# Source_Files.net
KiCad netlist of a schematic drawn in EasyEDA
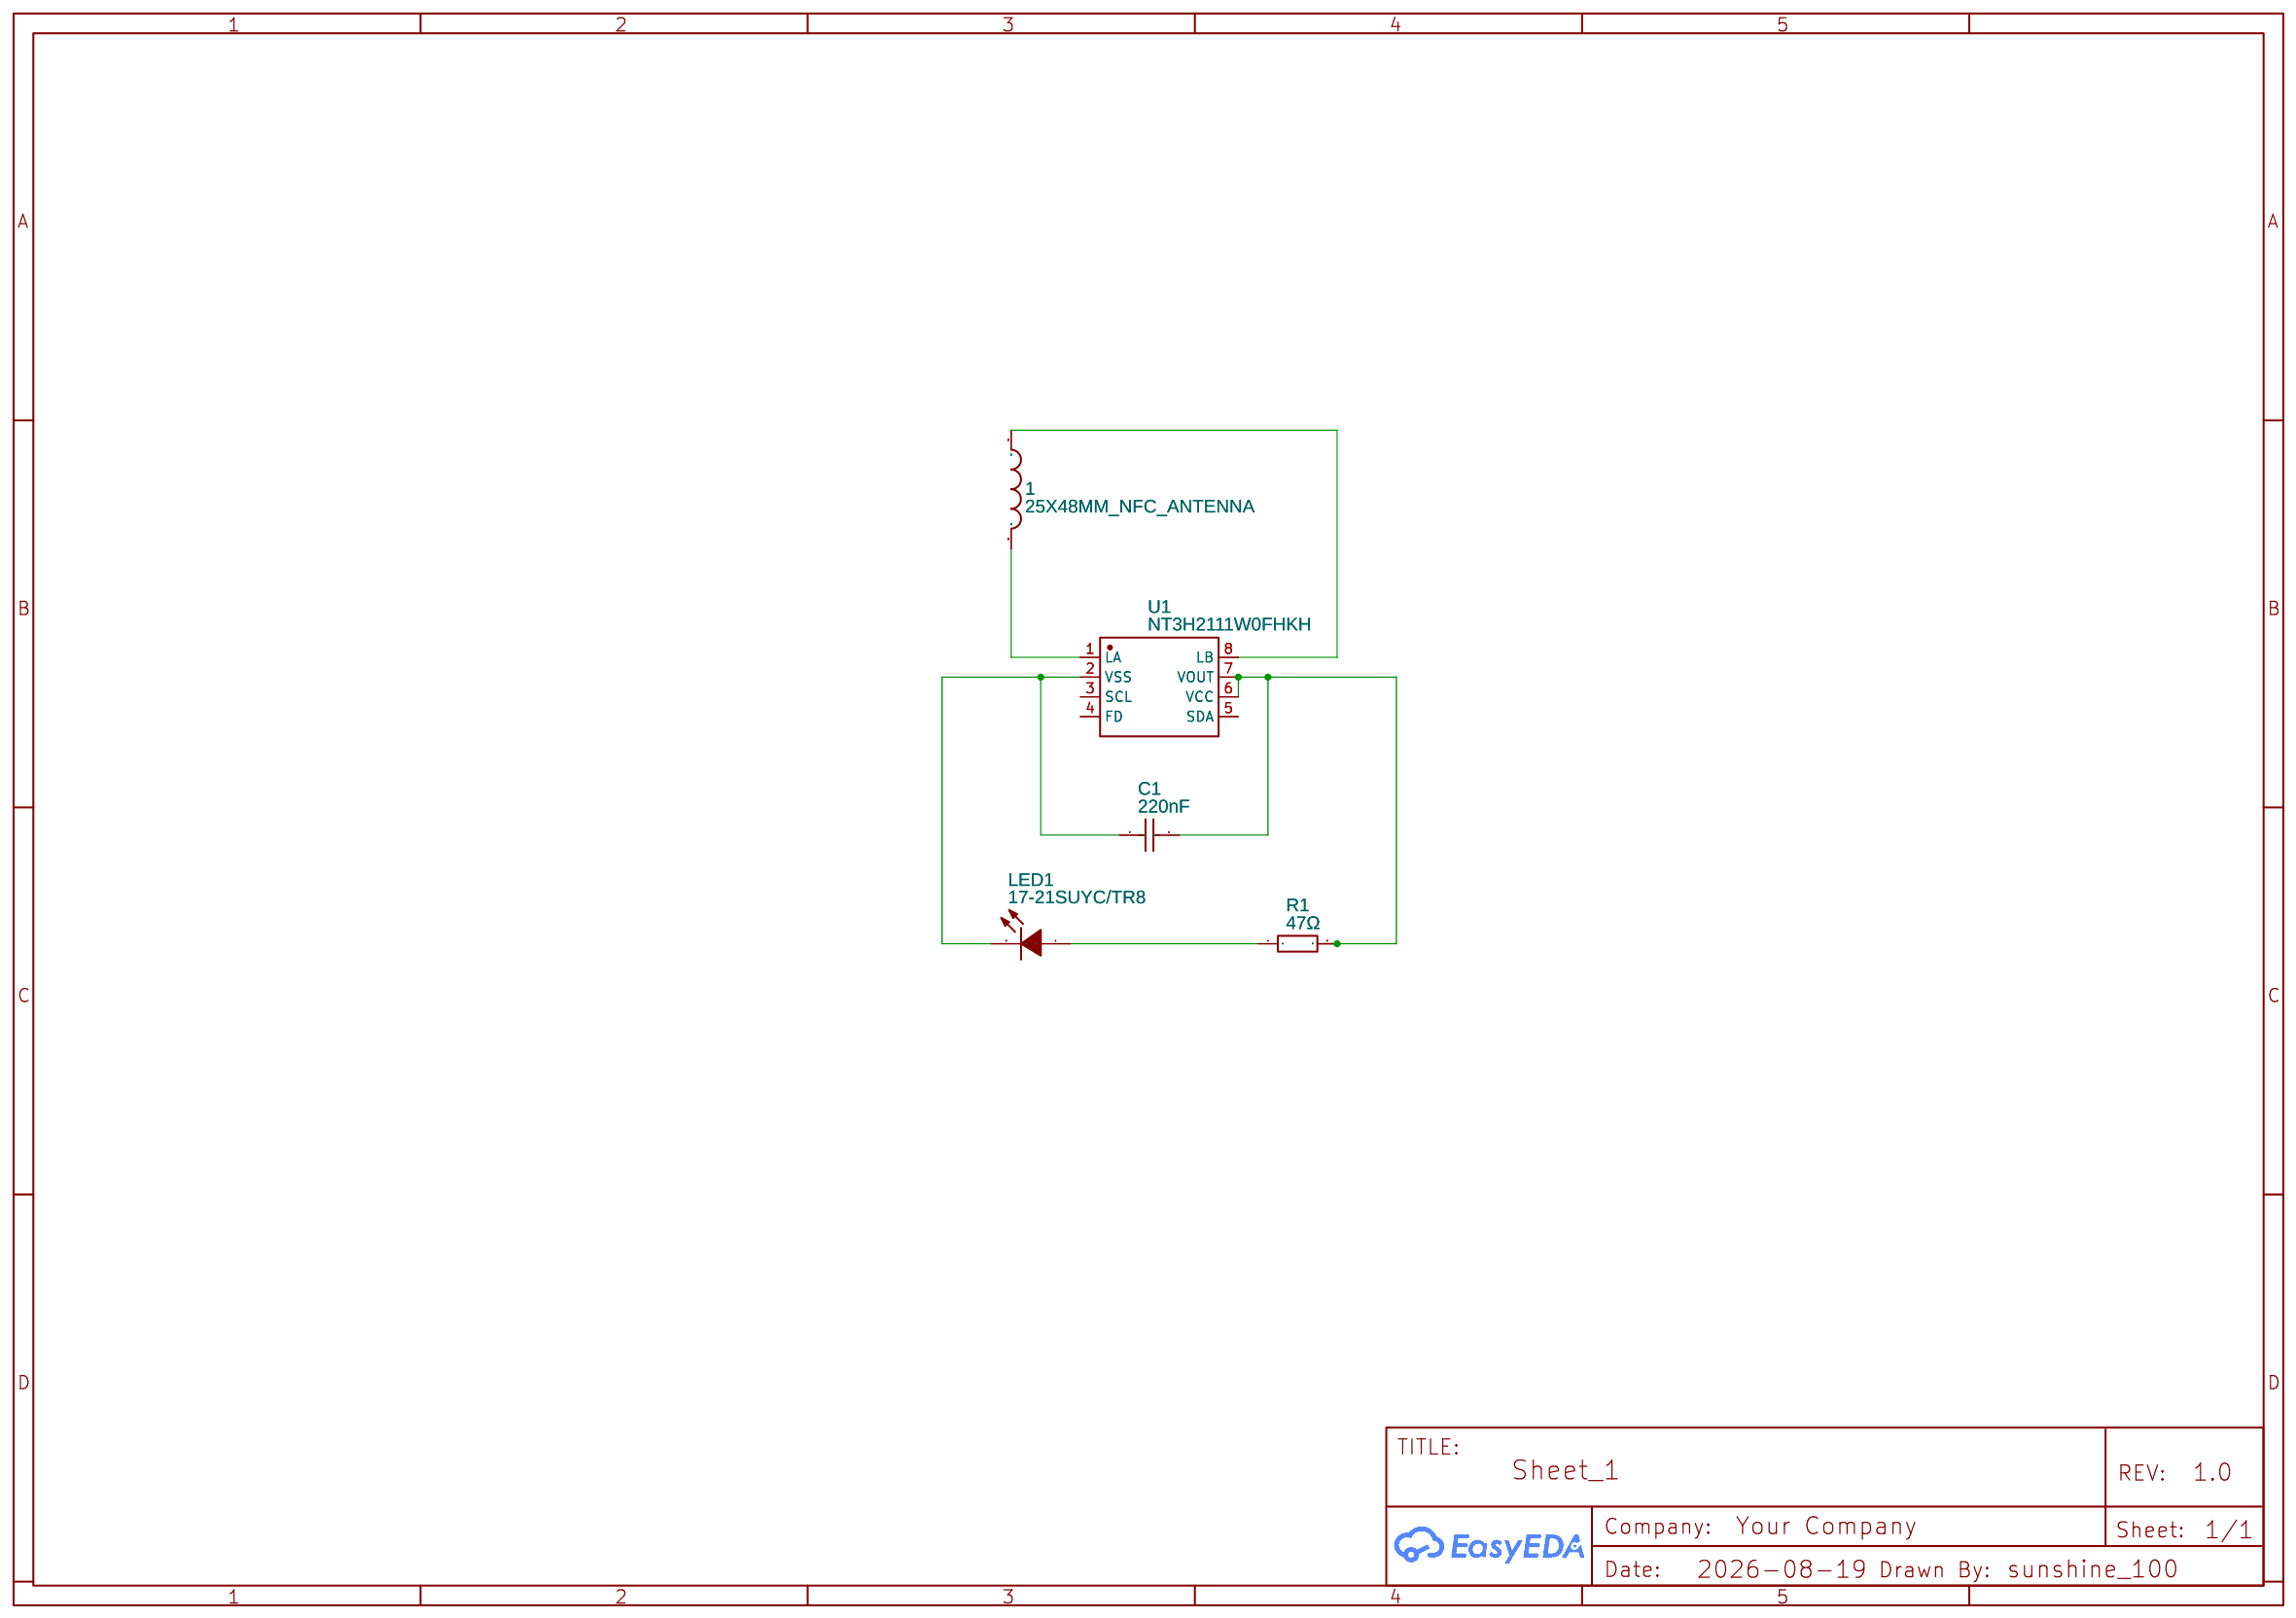
[diagram p0: schematic sheet]

(export (version "E")
  (design (tool "Eeschema 10.0.6"))
  (components
    (comp (ref "1") (value "25X48MM_NFC_ANTENNA") (libsource (lib "") (part "25X48MM_NFC_ANTENNA")))
    (comp (ref "C1")
      (value "220nF")
      (fields
        (field (name "Manufacturer Part") "CL10B224KA8NNNC")
        (field (name "Manufacturer") "SAMSUNG(三星)")
      )
      (libsource (lib "") (part "CL10B224KA8NNNC"))
    )
    (comp (ref "LED1")
      (value "17-21SUYC/TR8")
      (fields (field (name "Manufacturer Part") "KT-0805黄灯") (field (name "Manufacturer") "KENTO"))
      (libsource (lib "") (part "17-21SUYC/TR8"))
    )
    (comp (ref "R1")
      (value "47Ω")
      (fields
        (field (name "Manufacturer Part") "0603WAF470JT5E")
        (field (name "Manufacturer") "UNI-ROYAL(厚声)")
      )
      (libsource (lib "") (part "0603WAF470JT5E"))
    )
    (comp (ref "U1")
      (value "NT3H2111W0FHKH")
      (fields (field (name "Manufacturer") "NXP(恩智浦)"))
      (libsource (lib "") (part "NT3H2111W0FHKH"))
    )
  )
  (nets
    (net (code "1") (name "Net-(LED1-+)") (class "Default")
      (node (ref "LED1") (pin "1") (pinfunction "+_1") (pintype "unspecified"))
      (node (ref "R1") (pin "1") (pinfunction "1_1") (pintype "input"))
    )
    (net (code "2") (name "Net-(LED1--)") (class "Default")
      (node (ref "C1") (pin "1") (pinfunction "1_1") (pintype "input"))
      (node (ref "LED1") (pin "2") (pinfunction "-_2") (pintype "unspecified"))
      (node (ref "U1") (pin "2") (pinfunction "VSS_2") (pintype "unspecified"))
    )
    (net (code "3") (name "Net-(U1-LA)") (class "Default")
      (node (ref "1") (pin "P$2") (pinfunction "P$2_P$2") (pintype "bidirectional"))
      (node (ref "U1") (pin "1") (pinfunction "LA_1") (pintype "unspecified"))
    )
    (net (code "4") (name "Net-(U1-LB)") (class "Default")
      (node (ref "1") (pin "P$1") (pinfunction "P$1_P$1") (pintype "bidirectional"))
      (node (ref "U1") (pin "8") (pinfunction "LB_8") (pintype "unspecified"))
    )
    (net (code "5") (name "Net-(U1-VCC)") (class "Default")
      (node (ref "C1") (pin "2") (pinfunction "2_2") (pintype "input"))
      (node (ref "R1") (pin "2") (pinfunction "2_2") (pintype "input"))
      (node (ref "U1") (pin "6") (pinfunction "VCC_6") (pintype "unspecified"))
      (node (ref "U1") (pin "7") (pinfunction "VOUT_7") (pintype "unspecified"))
    )
    (net (code "6") (name "unconnected-(U1-FD-Pad4)") (class "Default")
      (node (ref "U1") (pin "4") (pinfunction "FD_4") (pintype "unspecified"))
    )
    (net (code "7") (name "unconnected-(U1-SCL-Pad3)") (class "Default")
      (node (ref "U1") (pin "3") (pinfunction "SCL_3") (pintype "unspecified"))
    )
    (net (code "8") (name "unconnected-(U1-SDA-Pad5)") (class "Default")
      (node (ref "U1") (pin "5") (pinfunction "SDA_5") (pintype "unspecified"))
    )
  )
)
